# DIYpiano.net
KiCad netlist of a schematic drawn in EAGLE
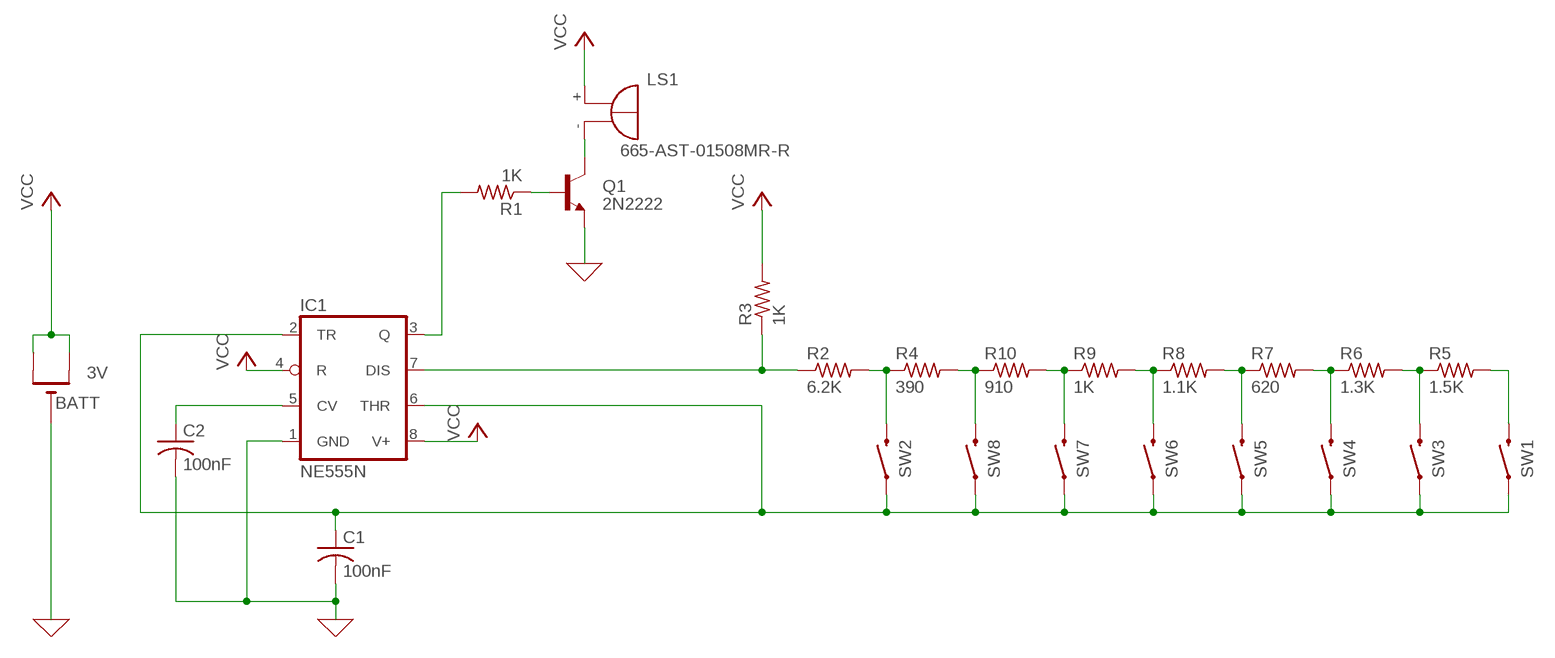
[diagram p0: schematic, sheet 1]

(export (version "E")
  (design (tool "Eeschema 10.0.6"))
  (components
    (comp (ref "BATT")
      (value "3V")
      (footprint "eagle-import:CR1220-THM")
      (fields (field (name "MF") "KEYSTONE ELECTR") (field (name "MPN") "3001"))
      (libsource (lib "eagle-import") (part "CR1220THM"))
    )
    (comp (ref "C1")
      (value "100nF")
      (footprint "eagle-import:C025-025X050")
      (libsource (lib "eagle-import") (part "C-US025-025X050"))
    )
    (comp (ref "C2")
      (value "100nF")
      (footprint "eagle-import:C025-025X050")
      (libsource (lib "eagle-import") (part "C-US025-025X050"))
    )
    (comp (ref "IC1")
      (value "NE555N")
      (footprint "eagle-import:DIL08")
      (fields (field (name "MPN") "TLC555CP"))
      (libsource (lib "eagle-import") (part "555NNE"))
    )
    (comp (ref "LS1")
      (value "F/HMB")
      (footprint "eagle-import:F_HMB")
      (fields (field (name "MOUSER#") "665-AST-01508MR-R"))
      (libsource (lib "eagle-import") (part "F/HMB"))
    )
    (comp (ref "Q1")
      (value "2N2222")
      (footprint "eagle-import:TO92-E1")
      (fields (field (name "MF") "FAIRCHILD SEMICONDUCTOR") (field (name "MPN") "PN2222ATF"))
      (libsource (lib "eagle-import") (part "-NPN-TO92-E1"))
    )
    (comp (ref "R1")
      (value "1K")
      (footprint "eagle-import:0207_10")
      (libsource (lib "eagle-import") (part "R-US_0207/10"))
    )
    (comp (ref "R2")
      (value "6.2K")
      (footprint "eagle-import:0207_10")
      (libsource (lib "eagle-import") (part "R-US_0207/10"))
    )
    (comp (ref "R3")
      (value "1K")
      (footprint "eagle-import:0207_10")
      (libsource (lib "eagle-import") (part "R-US_0207/10"))
    )
    (comp (ref "R4")
      (value "390")
      (footprint "eagle-import:0207_10")
      (libsource (lib "eagle-import") (part "R-US_0207/10"))
    )
    (comp (ref "R5")
      (value "1.5K")
      (footprint "eagle-import:0207_10")
      (libsource (lib "eagle-import") (part "R-US_0207/10"))
    )
    (comp (ref "R6")
      (value "1.3K")
      (footprint "eagle-import:0207_10")
      (libsource (lib "eagle-import") (part "R-US_0207/10"))
    )
    (comp (ref "R7")
      (value "620")
      (footprint "eagle-import:0207_10")
      (libsource (lib "eagle-import") (part "R-US_0207/10"))
    )
    (comp (ref "R8")
      (value "1.1K")
      (footprint "eagle-import:0207_10")
      (libsource (lib "eagle-import") (part "R-US_0207/10"))
    )
    (comp (ref "R9")
      (value "1K")
      (footprint "eagle-import:0207_10")
      (libsource (lib "eagle-import") (part "R-US_0207/10"))
    )
    (comp (ref "R10")
      (value "910")
      (footprint "eagle-import:0207_10")
      (libsource (lib "eagle-import") (part "R-US_0207/10"))
    )
    (comp (ref "SW1")
      (value "MOMENTARY-SWITCH-SPST-PTH-6.0MM")
      (footprint "eagle-import:TACTILE_SWITCH_PTH_6.0MM")
      (libsource (lib "eagle-import") (part "MOMENTARY-SWITCH-SPST-PTH-6.0MM"))
    )
    (comp (ref "SW2")
      (value "MOMENTARY-SWITCH-SPST-PTH-6.0MM")
      (footprint "eagle-import:TACTILE_SWITCH_PTH_6.0MM")
      (libsource (lib "eagle-import") (part "MOMENTARY-SWITCH-SPST-PTH-6.0MM"))
    )
    (comp (ref "SW3")
      (value "MOMENTARY-SWITCH-SPST-PTH-6.0MM")
      (footprint "eagle-import:TACTILE_SWITCH_PTH_6.0MM")
      (libsource (lib "eagle-import") (part "MOMENTARY-SWITCH-SPST-PTH-6.0MM"))
    )
    (comp (ref "SW4")
      (value "MOMENTARY-SWITCH-SPST-PTH-6.0MM")
      (footprint "eagle-import:TACTILE_SWITCH_PTH_6.0MM")
      (libsource (lib "eagle-import") (part "MOMENTARY-SWITCH-SPST-PTH-6.0MM"))
    )
    (comp (ref "SW5")
      (value "MOMENTARY-SWITCH-SPST-PTH-6.0MM")
      (footprint "eagle-import:TACTILE_SWITCH_PTH_6.0MM")
      (libsource (lib "eagle-import") (part "MOMENTARY-SWITCH-SPST-PTH-6.0MM"))
    )
    (comp (ref "SW6")
      (value "MOMENTARY-SWITCH-SPST-PTH-6.0MM")
      (footprint "eagle-import:TACTILE_SWITCH_PTH_6.0MM")
      (libsource (lib "eagle-import") (part "MOMENTARY-SWITCH-SPST-PTH-6.0MM"))
    )
    (comp (ref "SW7")
      (value "MOMENTARY-SWITCH-SPST-PTH-6.0MM")
      (footprint "eagle-import:TACTILE_SWITCH_PTH_6.0MM")
      (libsource (lib "eagle-import") (part "MOMENTARY-SWITCH-SPST-PTH-6.0MM"))
    )
    (comp (ref "SW8")
      (value "MOMENTARY-SWITCH-SPST-PTH-6.0MM")
      (footprint "eagle-import:TACTILE_SWITCH_PTH_6.0MM")
      (libsource (lib "eagle-import") (part "MOMENTARY-SWITCH-SPST-PTH-6.0MM"))
    )
  )
  (nets
    (net (code "1") (name "GND") (class "Default")
      (node (ref "BATT") (pin "-") (pinfunction "-_-") (pintype "passive"))
      (node (ref "C1") (pin "2") (pinfunction "2_2") (pintype "passive"))
      (node (ref "C2") (pin "2") (pinfunction "2_2") (pintype "passive"))
      (node (ref "IC1") (pin "1") (pinfunction "GND_1") (pintype "power_in"))
      (node (ref "Q1") (pin "3") (pinfunction "E_3") (pintype "passive"))
    )
    (net (code "2") (name "Net-(IC1-CV)") (class "Default")
      (node (ref "C2") (pin "1") (pinfunction "1_1") (pintype "passive"))
      (node (ref "IC1") (pin "5") (pinfunction "CV_5") (pintype "input"))
    )
    (net (code "3") (name "Net-(IC1-DIS)") (class "Default")
      (node (ref "IC1") (pin "7") (pinfunction "DIS_7") (pintype "input"))
      (node (ref "R2") (pin "1") (pinfunction "1_1") (pintype "passive"))
      (node (ref "R3") (pin "1") (pinfunction "1_1") (pintype "passive"))
    )
    (net (code "4") (name "Net-(IC1-Q)") (class "Default")
      (node (ref "IC1") (pin "3") (pinfunction "Q_3") (pintype "output"))
      (node (ref "R1") (pin "2") (pinfunction "2_2") (pintype "passive"))
    )
    (net (code "5") (name "Net-(IC1-THR)") (class "Default")
      (node (ref "C1") (pin "1") (pinfunction "1_1") (pintype "passive"))
      (node (ref "IC1") (pin "2") (pinfunction "TR_2") (pintype "input"))
      (node (ref "IC1") (pin "6") (pinfunction "THR_6") (pintype "input"))
      (node (ref "SW1") (pin "1") (pinfunction "1_1") (pintype "passive"))
      (node (ref "SW2") (pin "1") (pinfunction "1_1") (pintype "passive"))
      (node (ref "SW3") (pin "1") (pinfunction "1_1") (pintype "passive"))
      (node (ref "SW4") (pin "1") (pinfunction "1_1") (pintype "passive"))
      (node (ref "SW5") (pin "1") (pinfunction "1_1") (pintype "passive"))
      (node (ref "SW6") (pin "1") (pinfunction "1_1") (pintype "passive"))
      (node (ref "SW7") (pin "1") (pinfunction "1_1") (pintype "passive"))
      (node (ref "SW8") (pin "1") (pinfunction "1_1") (pintype "passive"))
    )
    (net (code "6") (name "Net-(Q1-B)") (class "Default")
      (node (ref "Q1") (pin "2") (pinfunction "B_2") (pintype "passive"))
      (node (ref "R1") (pin "1") (pinfunction "1_1") (pintype "passive"))
    )
    (net (code "7") (name "Net-(Q1-C)") (class "Default")
      (node (ref "LS1") (pin "-") (pinfunction "-_-") (pintype "passive"))
      (node (ref "Q1") (pin "1") (pinfunction "C_1") (pintype "passive"))
    )
    (net (code "8") (name "Net-(SW1-2)") (class "Default")
      (node (ref "R5") (pin "2") (pinfunction "2_2") (pintype "passive"))
      (node (ref "SW1") (pin "3") (pinfunction "2_3") (pintype "passive"))
    )
    (net (code "9") (name "Net-(SW2-2)") (class "Default")
      (node (ref "R2") (pin "2") (pinfunction "2_2") (pintype "passive"))
      (node (ref "R4") (pin "1") (pinfunction "1_1") (pintype "passive"))
      (node (ref "SW2") (pin "3") (pinfunction "2_3") (pintype "passive"))
    )
    (net (code "10") (name "Net-(SW3-2)") (class "Default")
      (node (ref "R5") (pin "1") (pinfunction "1_1") (pintype "passive"))
      (node (ref "R6") (pin "2") (pinfunction "2_2") (pintype "passive"))
      (node (ref "SW3") (pin "3") (pinfunction "2_3") (pintype "passive"))
    )
    (net (code "11") (name "Net-(SW4-2)") (class "Default")
      (node (ref "R6") (pin "1") (pinfunction "1_1") (pintype "passive"))
      (node (ref "R7") (pin "2") (pinfunction "2_2") (pintype "passive"))
      (node (ref "SW4") (pin "3") (pinfunction "2_3") (pintype "passive"))
    )
    (net (code "12") (name "Net-(SW5-2)") (class "Default")
      (node (ref "R7") (pin "1") (pinfunction "1_1") (pintype "passive"))
      (node (ref "R8") (pin "2") (pinfunction "2_2") (pintype "passive"))
      (node (ref "SW5") (pin "3") (pinfunction "2_3") (pintype "passive"))
    )
    (net (code "13") (name "Net-(SW6-2)") (class "Default")
      (node (ref "R8") (pin "1") (pinfunction "1_1") (pintype "passive"))
      (node (ref "R9") (pin "2") (pinfunction "2_2") (pintype "passive"))
      (node (ref "SW6") (pin "3") (pinfunction "2_3") (pintype "passive"))
    )
    (net (code "14") (name "Net-(SW7-2)") (class "Default")
      (node (ref "R10") (pin "2") (pinfunction "2_2") (pintype "passive"))
      (node (ref "R9") (pin "1") (pinfunction "1_1") (pintype "passive"))
      (node (ref "SW7") (pin "3") (pinfunction "2_3") (pintype "passive"))
    )
    (net (code "15") (name "Net-(SW8-2)") (class "Default")
      (node (ref "R10") (pin "1") (pinfunction "1_1") (pintype "passive"))
      (node (ref "R4") (pin "2") (pinfunction "2_2") (pintype "passive"))
      (node (ref "SW8") (pin "3") (pinfunction "2_3") (pintype "passive"))
    )
    (net (code "16") (name "VCC") (class "Default")
      (node (ref "BATT") (pin "+1") (pinfunction "+_+1") (pintype "passive"))
      (node (ref "BATT") (pin "+2") (pinfunction "+1_+2") (pintype "passive"))
      (node (ref "IC1") (pin "4") (pinfunction "R_4") (pintype "input"))
      (node (ref "IC1") (pin "8") (pinfunction "V+_8") (pintype "power_in"))
      (node (ref "LS1") (pin "+") (pinfunction "+_+") (pintype "passive"))
      (node (ref "R3") (pin "2") (pinfunction "2_2") (pintype "passive"))
    )
  )
)
